# uSimar_PCB_V0.net
KiCad netlist of a schematic drawn in Altium Designer
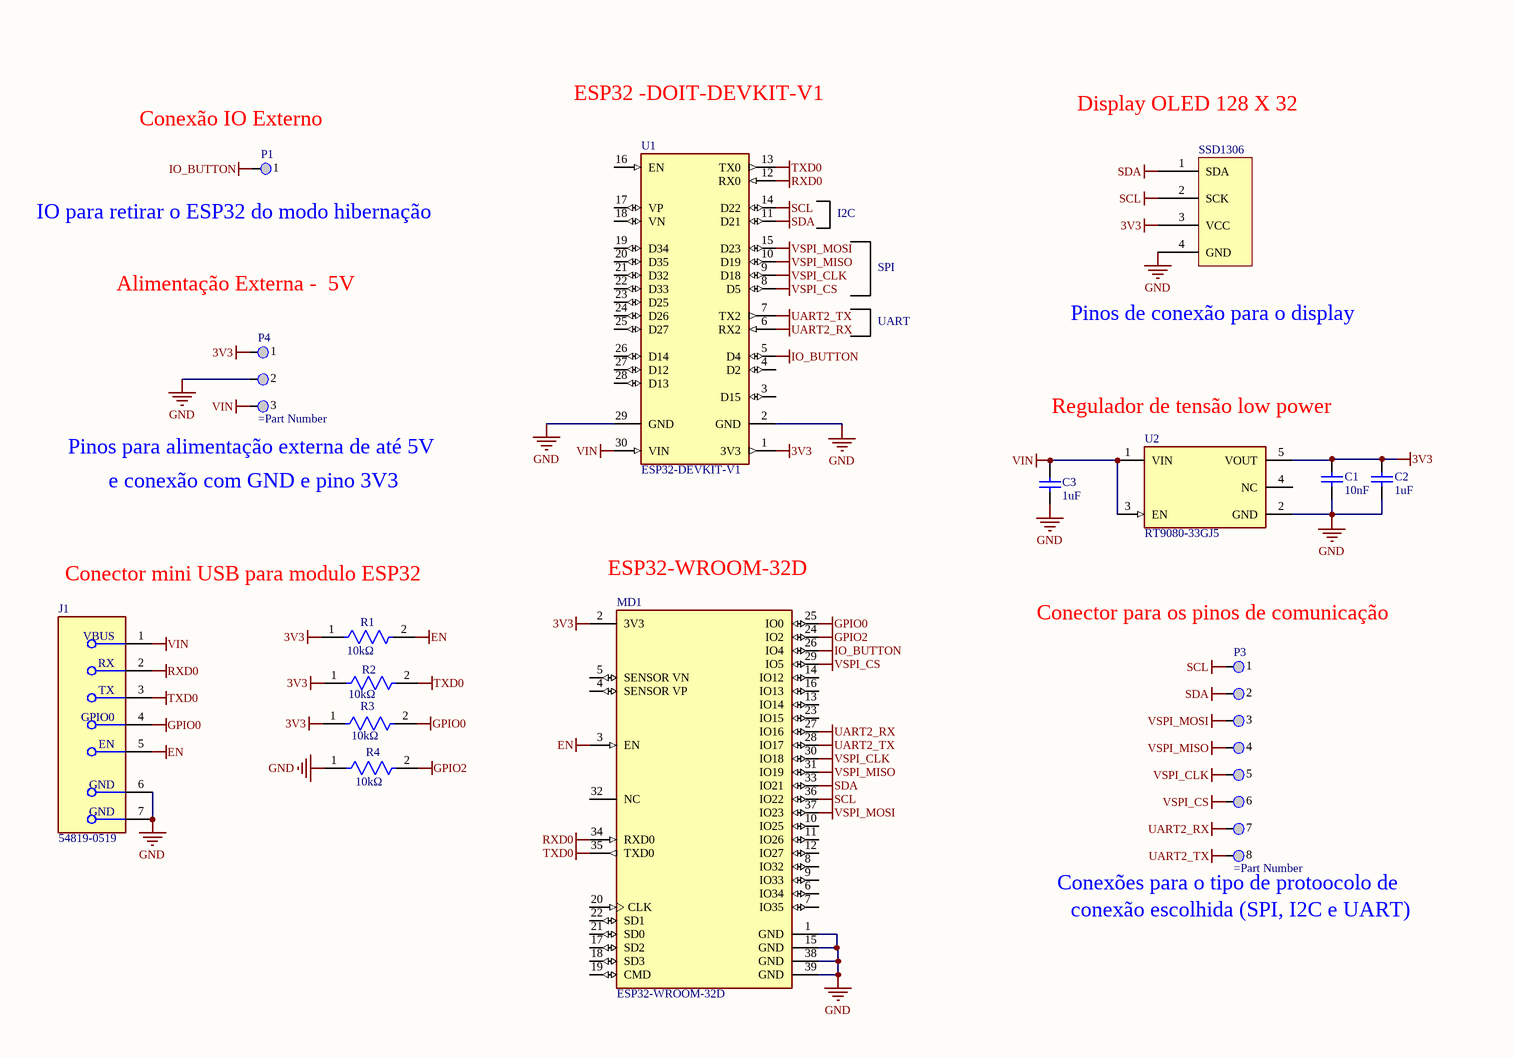
[diagram p0: uSimar_PCB_V0.SchDoc, left]

(export (version "E")
  (design (tool "Eeschema 10.0.6"))
  (components
    (comp (ref "C1")
      (value "10nF")
      (footprint "C_0805")
      (description "0805 C 10nF Ceramic Multilayer Capacitor; 200 VDC; +125degC; X7R Dielec; +/-10%")
      (fields
        (field (name "MANUFACTURER") "KEMET")
        (field (name "MANUFACTURER PART NUMBER") "C0805C103K2RACTU")
      )
      (libsource (lib "uSimar_Components") (part "C0805C103K2RACTU"))
    )
    (comp (ref "C2")
      (value "1uF")
      (footprint "C_0805")
      (description "Cap Ceramic 1uF 16V X5R 10% SMD 0805 85C Plastic T/R")
      (fields
        (field (name "MANUFACTURER") "KEMET")
        (field (name "MANUFACTURER PART NUMBER") "C0805C105K4PACTU")
      )
      (libsource (lib "uSimar_Components") (part "C0805C105K4PACTU"))
    )
    (comp (ref "C3")
      (value "1uF")
      (footprint "C_0805")
      (description "Cap Ceramic 1uF 16V X5R 10% SMD 0805 85C Plastic T/R")
      (fields
        (field (name "MANUFACTURER") "KEMET")
        (field (name "MANUFACTURER PART NUMBER") "C0805C105K4PACTU")
      )
      (libsource (lib "uSimar_Components") (part "C0805C105K4PACTU"))
    )
    (comp (ref "J1")
      (value "54819-0519")
      (footprint "FP-54819-0519-MFG")
      (description "CONN RCPT USB2.0 MINI B 5P R/A")
      (libsource (lib "uSimar_Components") (part "CMP-04767-000009-1"))
    )
    (comp (ref "MD1")
      (value "ESP32-WROOM-32D")
      (footprint "FP-ESP32-WROOM-32D-MFG")
      (description "WIFI MODULE 32MBITS SPI FLASH")
      (fields
        (field (name "OCTOPART") "https://octopart.com/esp32-wroom-32d-espressif+systems-91040050")
        (field (name "MANUFACTURER") "Espressif Systems")
      )
      (libsource (lib "uSimar_Components") (part "CMP-194065-000003-1"))
    )
    (comp (ref "P1")
      (value "~")
      (footprint "HDR1X1")
      (description "Header, 1-Pin")
      (libsource (lib "uSimar_Components") (part "Header 1"))
    )
    (comp (ref "P3")
      (value "~")
      (footprint "HDR1X8")
      (description "Header, 8-Pin")
      (libsource (lib "uSimar_Components") (part "Header 8"))
    )
    (comp (ref "P4")
      (value "~")
      (footprint "HDR1X3")
      (description "Header, 3-Pin")
      (libsource (lib "uSimar_Components") (part "Header 3"))
    )
    (comp (ref "R1")
      (value "10kΩ")
      (footprint "FP-CRCW0805-e3-IPC_C")
      (description "RES Thick Film, 10kΩ, 1%, 0.125W, 100ppm/°C, 0805")
      (fields (field (name "TOLERANCE") "1%"))
      (libsource (lib "uSimar_Components") (part "CMP-2001-04908-2"))
    )
    (comp (ref "R2")
      (value "10kΩ")
      (footprint "FP-CRCW0805-e3-IPC_C")
      (description "RES Thick Film, 10kΩ, 1%, 0.125W, 100ppm/°C, 0805")
      (fields (field (name "TOLERANCE") "1%"))
      (libsource (lib "uSimar_Components") (part "CMP-2001-04908-2"))
    )
    (comp (ref "R3")
      (value "10kΩ")
      (footprint "FP-CRCW0805-e3-IPC_C")
      (description "RES Thick Film, 10kΩ, 1%, 0.125W, 100ppm/°C, 0805")
      (fields (field (name "TOLERANCE") "1%"))
      (libsource (lib "uSimar_Components") (part "CMP-2001-04908-2"))
    )
    (comp (ref "R4")
      (value "10kΩ")
      (footprint "FP-CRCW0805-e3-IPC_C")
      (description "RES Thick Film, 10kΩ, 1%, 0.125W, 100ppm/°C, 0805")
      (fields (field (name "TOLERANCE") "1%"))
      (libsource (lib "uSimar_Components") (part "CMP-2001-04908-2"))
    )
    (comp (ref "SSD1306")
      (value "SSD1306")
      (footprint "SSD1306 128X32_wiyhout top opverlay")
      (libsource (lib "uSimar_Components") (part "SSD1306"))
    )
    (comp (ref "U1")
      (value "ESP32-DEVKIT-V1")
      (footprint "MODULE_ESP32_DEVKIT_V1")
      (fields (field (name "MF") "Do it"))
      (libsource (lib "uSimar_Components") (part "ESP32-DEVKIT-V1"))
    )
    (comp (ref "U2")
      (value "RT9080-33GJ5")
      (footprint "FP-RT9080-33GJ5-IPC_B")
      (description "IC REG LIN 3.3V 600MA TSOT23-5")
      (libsource (lib "uSimar_Components") (part "CMP-79890-000003-1"))
    )
  )
  (nets
    (net (code "1") (name "3V3") (class "Default")
      (node (ref "C1") (pin "2") (pinfunction "2_2") (pintype "passive"))
      (node (ref "C2") (pin "2") (pinfunction "2_2") (pintype "passive"))
      (node (ref "MD1") (pin "2") (pinfunction "3V3_2") (pintype "power_in"))
      (node (ref "P4") (pin "1") (pinfunction "1_1") (pintype "passive"))
      (node (ref "R1") (pin "1") (pinfunction "1_1") (pintype "passive"))
      (node (ref "R2") (pin "1") (pinfunction "1_1") (pintype "passive"))
      (node (ref "R3") (pin "1") (pinfunction "1_1") (pintype "passive"))
      (node (ref "SSD1306") (pin "3") (pinfunction "VCC_3") (pintype "passive"))
      (node (ref "U1") (pin "1") (pinfunction "3V3_1") (pintype "output"))
      (node (ref "U2") (pin "5") (pinfunction "VOUT_5") (pintype "passive"))
    )
    (net (code "2") (name "EN") (class "Default")
      (node (ref "J1") (pin "5") (pinfunction "GND_5") (pintype "power_in"))
      (node (ref "MD1") (pin "3") (pinfunction "EN_3") (pintype "input"))
      (node (ref "R1") (pin "2") (pinfunction "2_2") (pintype "passive"))
    )
    (net (code "3") (name "GND") (class "Default")
      (node (ref "C1") (pin "1") (pinfunction "1_1") (pintype "passive"))
      (node (ref "C2") (pin "1") (pinfunction "1_1") (pintype "passive"))
      (node (ref "C3") (pin "1") (pinfunction "1_1") (pintype "passive"))
      (node (ref "J1") (pin "6") (pinfunction "MNT_1_6") (pintype "passive"))
      (node (ref "J1") (pin "7") (pinfunction "MNT_2_7") (pintype "passive"))
      (node (ref "MD1") (pin "1") (pinfunction "GND_1") (pintype "power_in"))
      (node (ref "MD1") (pin "15") (pinfunction "GND_15") (pintype "power_in"))
      (node (ref "MD1") (pin "38") (pinfunction "GND_38") (pintype "power_in"))
      (node (ref "MD1") (pin "39") (pinfunction "GND_39") (pintype "power_in"))
      (node (ref "P4") (pin "2") (pinfunction "2_2") (pintype "passive"))
      (node (ref "R4") (pin "1") (pinfunction "1_1") (pintype "passive"))
      (node (ref "SSD1306") (pin "4") (pinfunction "GND_4") (pintype "passive"))
      (node (ref "U1") (pin "2") (pinfunction "GND_2") (pintype "power_in"))
      (node (ref "U1") (pin "29") (pinfunction "GND_29") (pintype "power_in"))
      (node (ref "U2") (pin "2") (pinfunction "GND_2") (pintype "power_in"))
    )
    (net (code "4") (name "GPIO0") (class "Default")
      (node (ref "J1") (pin "4") (pinfunction "ID_4") (pintype "passive"))
      (node (ref "MD1") (pin "25") (pinfunction "IO0_25") (pintype "bidirectional"))
      (node (ref "R3") (pin "2") (pinfunction "2_2") (pintype "passive"))
    )
    (net (code "5") (name "GPIO2") (class "Default")
      (node (ref "MD1") (pin "24") (pinfunction "IO2_24") (pintype "bidirectional"))
      (node (ref "R4") (pin "2") (pinfunction "2_2") (pintype "passive"))
    )
    (net (code "6") (name "IO_BUTTON") (class "Default")
      (node (ref "MD1") (pin "26") (pinfunction "IO4_26") (pintype "bidirectional"))
      (node (ref "P1") (pin "1") (pinfunction "1_1") (pintype "passive"))
      (node (ref "U1") (pin "5") (pinfunction "D4_5") (pintype "bidirectional"))
    )
    (net (code "7") (name "RXD0") (class "Default")
      (node (ref "J1") (pin "2") (pinfunction "RX_2") (pintype "passive"))
      (node (ref "MD1") (pin "34") (pinfunction "RXD0_34") (pintype "input"))
      (node (ref "U1") (pin "12") (pinfunction "RX0_12") (pintype "input"))
    )
    (net (code "8") (name "SCL") (class "Default")
      (node (ref "MD1") (pin "36") (pinfunction "IO22_36") (pintype "bidirectional"))
      (node (ref "P3") (pin "1") (pinfunction "1_1") (pintype "passive"))
      (node (ref "SSD1306") (pin "2") (pinfunction "SCK_2") (pintype "passive"))
      (node (ref "U1") (pin "14") (pinfunction "D22_14") (pintype "bidirectional"))
    )
    (net (code "9") (name "SDA") (class "Default")
      (node (ref "MD1") (pin "33") (pinfunction "IO21_33") (pintype "bidirectional"))
      (node (ref "P3") (pin "2") (pinfunction "2_2") (pintype "passive"))
      (node (ref "SSD1306") (pin "1") (pinfunction "SDA_1") (pintype "passive"))
      (node (ref "U1") (pin "11") (pinfunction "D21_11") (pintype "bidirectional"))
    )
    (net (code "10") (name "TXD0") (class "Default")
      (node (ref "J1") (pin "3") (pinfunction "D+_3") (pintype "passive"))
      (node (ref "MD1") (pin "35") (pinfunction "TXD0_35") (pintype "output"))
      (node (ref "R2") (pin "2") (pinfunction "2_2") (pintype "passive"))
      (node (ref "U1") (pin "13") (pinfunction "TX0_13") (pintype "output"))
    )
    (net (code "11") (name "UART2_RX") (class "Default")
      (node (ref "MD1") (pin "27") (pinfunction "IO16_27") (pintype "bidirectional"))
      (node (ref "P3") (pin "7") (pinfunction "7_7") (pintype "passive"))
      (node (ref "U1") (pin "6") (pinfunction "RX2_6") (pintype "input"))
    )
    (net (code "12") (name "UART2_TX") (class "Default")
      (node (ref "MD1") (pin "28") (pinfunction "IO17_28") (pintype "bidirectional"))
      (node (ref "P3") (pin "8") (pinfunction "8_8") (pintype "passive"))
      (node (ref "U1") (pin "7") (pinfunction "TX2_7") (pintype "output"))
    )
    (net (code "13") (name "VIN") (class "Default")
      (node (ref "C3") (pin "2") (pinfunction "2_2") (pintype "passive"))
      (node (ref "J1") (pin "1") (pinfunction "VBUS_1") (pintype "power_in"))
      (node (ref "P4") (pin "3") (pinfunction "3_3") (pintype "passive"))
      (node (ref "U1") (pin "30") (pinfunction "VIN_30") (pintype "input"))
      (node (ref "U2") (pin "1") (pinfunction "VIN_1") (pintype "power_in"))
      (node (ref "U2") (pin "3") (pinfunction "EN_3") (pintype "input"))
    )
    (net (code "14") (name "VSPI_CLK") (class "Default")
      (node (ref "MD1") (pin "30") (pinfunction "IO18_30") (pintype "bidirectional"))
      (node (ref "P3") (pin "5") (pinfunction "5_5") (pintype "passive"))
      (node (ref "U1") (pin "9") (pinfunction "D18_9") (pintype "bidirectional"))
    )
    (net (code "15") (name "VSPI_CS") (class "Default")
      (node (ref "MD1") (pin "29") (pinfunction "IO5_29") (pintype "bidirectional"))
      (node (ref "P3") (pin "6") (pinfunction "6_6") (pintype "passive"))
      (node (ref "U1") (pin "8") (pinfunction "D5_8") (pintype "bidirectional"))
    )
    (net (code "16") (name "VSPI_MISO") (class "Default")
      (node (ref "MD1") (pin "31") (pinfunction "IO19_31") (pintype "bidirectional"))
      (node (ref "P3") (pin "4") (pinfunction "4_4") (pintype "passive"))
      (node (ref "U1") (pin "10") (pinfunction "D19_10") (pintype "bidirectional"))
    )
    (net (code "17") (name "VSPI_MOSI") (class "Default")
      (node (ref "MD1") (pin "37") (pinfunction "IO23_37") (pintype "bidirectional"))
      (node (ref "P3") (pin "3") (pinfunction "3_3") (pintype "passive"))
      (node (ref "U1") (pin "15") (pinfunction "D23_15") (pintype "bidirectional"))
    )
    (net (code "18") (name "unconnected-(MD1-CLK-Pad20)") (class "Default")
      (node (ref "MD1") (pin "20") (pinfunction "CLK_20") (pintype "input"))
    )
    (net (code "19") (name "unconnected-(MD1-CMD-Pad19)") (class "Default")
      (node (ref "MD1") (pin "19") (pinfunction "CMD_19") (pintype "bidirectional"))
    )
    (net (code "20") (name "unconnected-(MD1-IO12-Pad14)") (class "Default")
      (node (ref "MD1") (pin "14") (pinfunction "IO12_14") (pintype "bidirectional"))
    )
    (net (code "21") (name "unconnected-(MD1-IO13-Pad16)") (class "Default")
      (node (ref "MD1") (pin "16") (pinfunction "IO13_16") (pintype "bidirectional"))
    )
    (net (code "22") (name "unconnected-(MD1-IO14-Pad13)") (class "Default")
      (node (ref "MD1") (pin "13") (pinfunction "IO14_13") (pintype "bidirectional"))
    )
    (net (code "23") (name "unconnected-(MD1-IO15-Pad23)") (class "Default")
      (node (ref "MD1") (pin "23") (pinfunction "IO15_23") (pintype "bidirectional"))
    )
    (net (code "24") (name "unconnected-(MD1-IO25-Pad10)") (class "Default")
      (node (ref "MD1") (pin "10") (pinfunction "IO25_10") (pintype "bidirectional"))
    )
    (net (code "25") (name "unconnected-(MD1-IO26-Pad11)") (class "Default")
      (node (ref "MD1") (pin "11") (pinfunction "IO26_11") (pintype "bidirectional"))
    )
    (net (code "26") (name "unconnected-(MD1-IO27-Pad12)") (class "Default")
      (node (ref "MD1") (pin "12") (pinfunction "IO27_12") (pintype "bidirectional"))
    )
    (net (code "27") (name "unconnected-(MD1-IO32-Pad8)") (class "Default")
      (node (ref "MD1") (pin "8") (pinfunction "IO32_8") (pintype "bidirectional"))
    )
    (net (code "28") (name "unconnected-(MD1-IO33-Pad9)") (class "Default")
      (node (ref "MD1") (pin "9") (pinfunction "IO33_9") (pintype "bidirectional"))
    )
    (net (code "29") (name "unconnected-(MD1-IO34-Pad6)") (class "Default")
      (node (ref "MD1") (pin "6") (pinfunction "IO34_6") (pintype "bidirectional"))
    )
    (net (code "30") (name "unconnected-(MD1-IO35-Pad7)") (class "Default")
      (node (ref "MD1") (pin "7") (pinfunction "IO35_7") (pintype "bidirectional"))
    )
    (net (code "31") (name "unconnected-(MD1-NC-Pad32)") (class "Default")
      (node (ref "MD1") (pin "32") (pinfunction "NC_32") (pintype "passive"))
    )
    (net (code "32") (name "unconnected-(MD1-SD0-Pad21)") (class "Default")
      (node (ref "MD1") (pin "21") (pinfunction "SD0_21") (pintype "bidirectional"))
    )
    (net (code "33") (name "unconnected-(MD1-SD1-Pad22)") (class "Default")
      (node (ref "MD1") (pin "22") (pinfunction "SD1_22") (pintype "bidirectional"))
    )
    (net (code "34") (name "unconnected-(MD1-SD2-Pad17)") (class "Default")
      (node (ref "MD1") (pin "17") (pinfunction "SD2_17") (pintype "bidirectional"))
    )
    (net (code "35") (name "unconnected-(MD1-SD3-Pad18)") (class "Default")
      (node (ref "MD1") (pin "18") (pinfunction "SD3_18") (pintype "bidirectional"))
    )
    (net (code "36") (name "unconnected-(MD1-SENSOR_VN-Pad5)") (class "Default")
      (node (ref "MD1") (pin "5") (pinfunction "SENSOR_VN_5") (pintype "bidirectional"))
    )
    (net (code "37") (name "unconnected-(MD1-SENSOR_VP-Pad4)") (class "Default")
      (node (ref "MD1") (pin "4") (pinfunction "SENSOR_VP_4") (pintype "bidirectional"))
    )
    (net (code "38") (name "unconnected-(U1-D2-Pad4)") (class "Default")
      (node (ref "U1") (pin "4") (pinfunction "D2_4") (pintype "bidirectional"))
    )
    (net (code "39") (name "unconnected-(U1-D12-Pad27)") (class "Default")
      (node (ref "U1") (pin "27") (pinfunction "D12_27") (pintype "bidirectional"))
    )
    (net (code "40") (name "unconnected-(U1-D13-Pad28)") (class "Default")
      (node (ref "U1") (pin "28") (pinfunction "D13_28") (pintype "bidirectional"))
    )
    (net (code "41") (name "unconnected-(U1-D14-Pad26)") (class "Default")
      (node (ref "U1") (pin "26") (pinfunction "D14_26") (pintype "bidirectional"))
    )
    (net (code "42") (name "unconnected-(U1-D15-Pad3)") (class "Default")
      (node (ref "U1") (pin "3") (pinfunction "D15_3") (pintype "bidirectional"))
    )
    (net (code "43") (name "unconnected-(U1-D25-Pad23)") (class "Default")
      (node (ref "U1") (pin "23") (pinfunction "D25_23") (pintype "bidirectional"))
    )
    (net (code "44") (name "unconnected-(U1-D26-Pad24)") (class "Default")
      (node (ref "U1") (pin "24") (pinfunction "D26_24") (pintype "bidirectional"))
    )
    (net (code "45") (name "unconnected-(U1-D27-Pad25)") (class "Default")
      (node (ref "U1") (pin "25") (pinfunction "D27_25") (pintype "bidirectional"))
    )
    (net (code "46") (name "unconnected-(U1-D32-Pad21)") (class "Default")
      (node (ref "U1") (pin "21") (pinfunction "D32_21") (pintype "bidirectional"))
    )
    (net (code "47") (name "unconnected-(U1-D33-Pad22)") (class "Default")
      (node (ref "U1") (pin "22") (pinfunction "D33_22") (pintype "bidirectional"))
    )
    (net (code "48") (name "unconnected-(U1-D34-Pad19)") (class "Default")
      (node (ref "U1") (pin "19") (pinfunction "D34_19") (pintype "bidirectional"))
    )
    (net (code "49") (name "unconnected-(U1-D35-Pad20)") (class "Default")
      (node (ref "U1") (pin "20") (pinfunction "D35_20") (pintype "bidirectional"))
    )
    (net (code "50") (name "unconnected-(U1-EN-Pad16)") (class "Default")
      (node (ref "U1") (pin "16") (pinfunction "EN_16") (pintype "input"))
    )
    (net (code "51") (name "unconnected-(U1-VN-Pad18)") (class "Default")
      (node (ref "U1") (pin "18") (pinfunction "VN_18") (pintype "bidirectional"))
    )
    (net (code "52") (name "unconnected-(U1-VP-Pad17)") (class "Default")
      (node (ref "U1") (pin "17") (pinfunction "VP_17") (pintype "bidirectional"))
    )
    (net (code "53") (name "unconnected-(U2-NC-Pad4)") (class "Default")
      (node (ref "U2") (pin "4") (pinfunction "NC_4") (pintype "passive"))
    )
  )
)
